# SparkFun_Buck-Boost.net
KiCad netlist of a schematic drawn in EAGLE
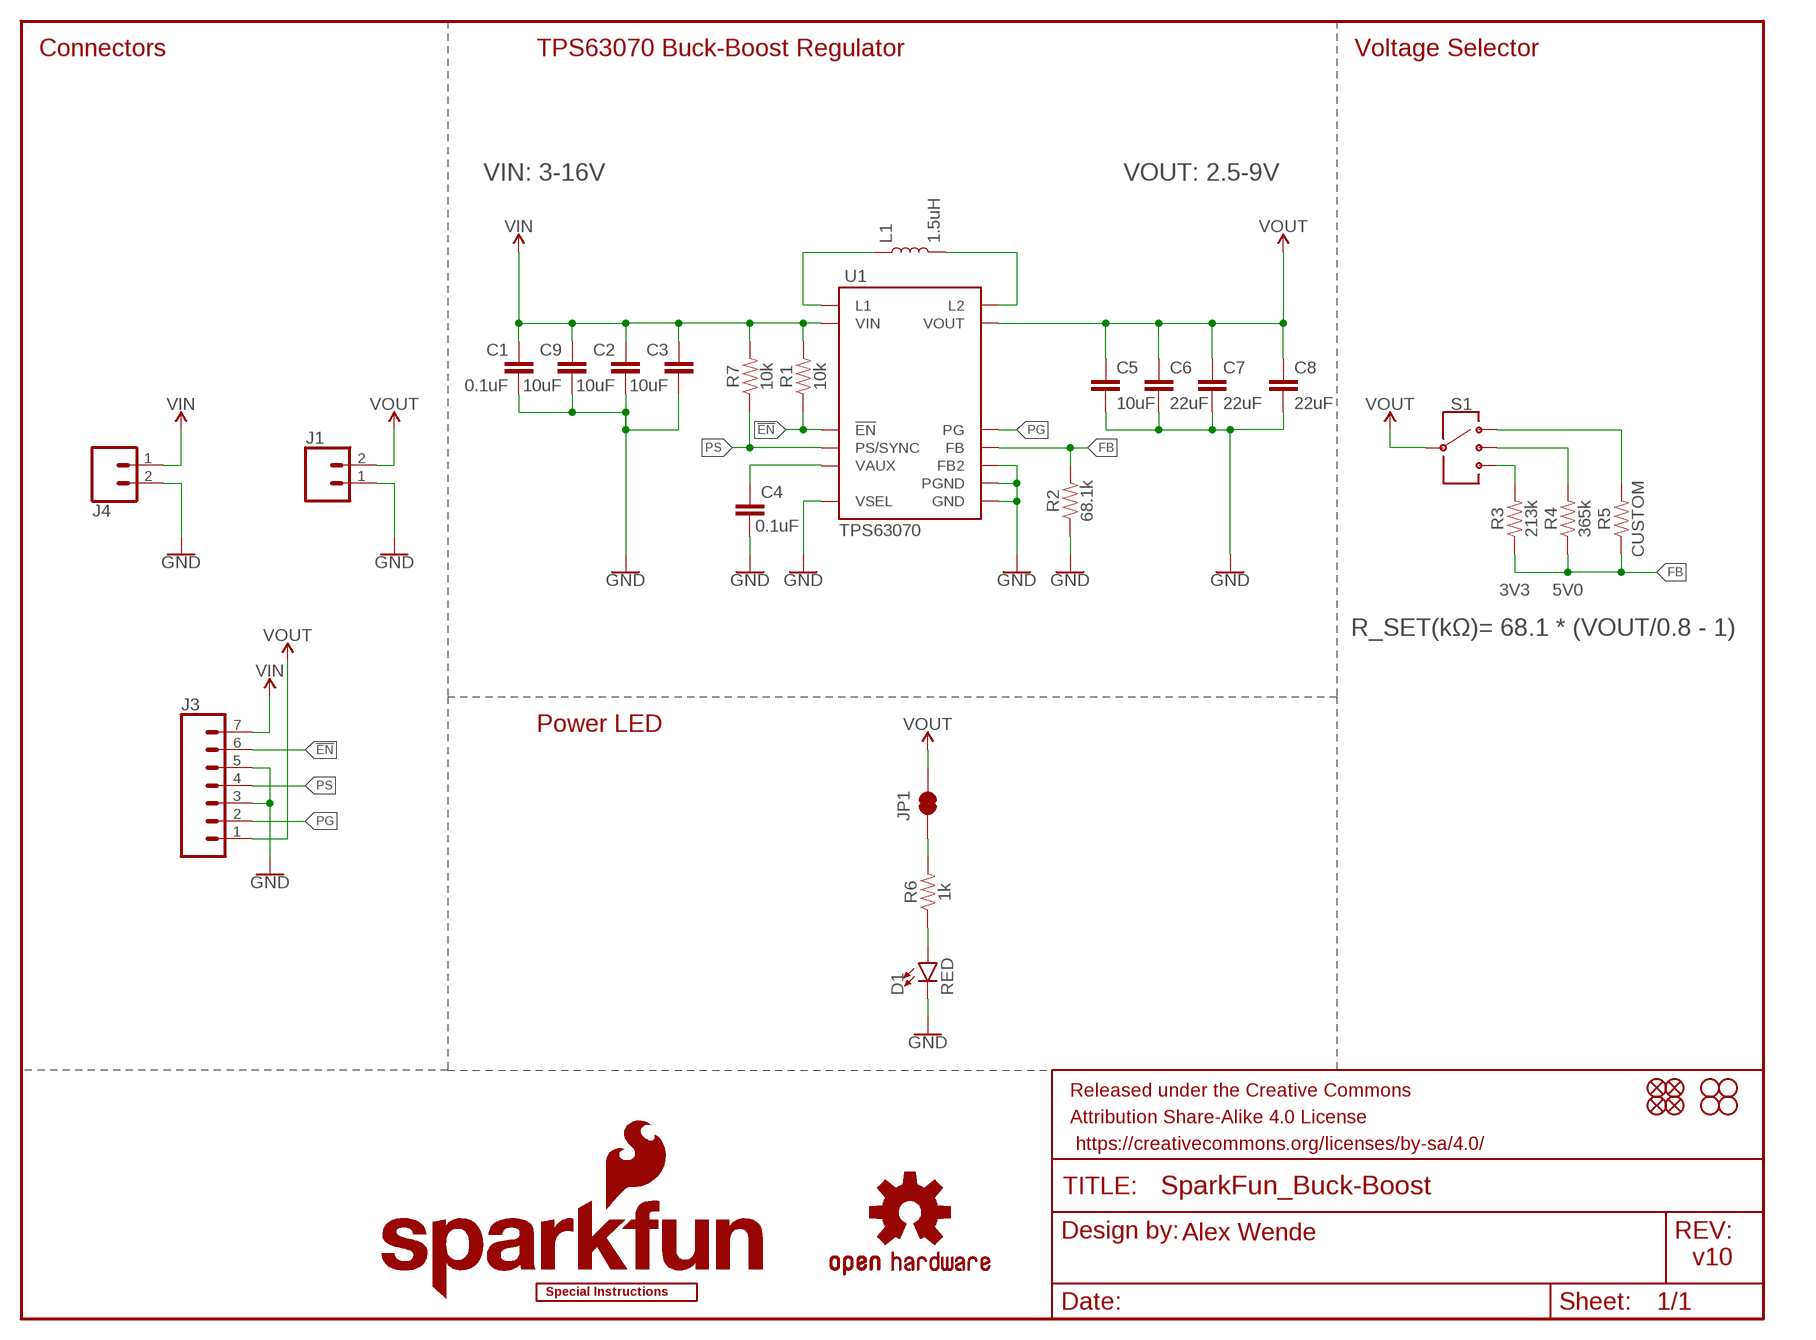
[diagram p0: schematic, sheet 1]

(export (version "E")
  (design (tool "Eeschema 10.0.6"))
  (components
    (comp (ref "C1")
      (value "0.1uF")
      (footprint "eagle-import:0603")
      (libsource (lib "eagle-import") (part "0.1UF-0603-25V-(+80/-20%)"))
    )
    (comp (ref "C2")
      (value "10uF")
      (footprint "eagle-import:0805")
      (libsource (lib "eagle-import") (part "10UF-0805-25V-10%"))
    )
    (comp (ref "C3")
      (value "10uF")
      (footprint "eagle-import:0805")
      (libsource (lib "eagle-import") (part "10UF-0805-25V-10%"))
    )
    (comp (ref "C4")
      (value "0.1uF")
      (footprint "eagle-import:0603")
      (libsource (lib "eagle-import") (part "0.1UF-0603-25V-(+80/-20%)"))
    )
    (comp (ref "C5")
      (value "10uF")
      (footprint "eagle-import:0805")
      (libsource (lib "eagle-import") (part "10UF-0805-25V-10%"))
    )
    (comp (ref "C6")
      (value "22uF")
      (footprint "eagle-import:0805")
      (libsource (lib "eagle-import") (part "22UF-0805-16V-20%"))
    )
    (comp (ref "C7")
      (value "22uF")
      (footprint "eagle-import:0805")
      (libsource (lib "eagle-import") (part "22UF-0805-16V-20%"))
    )
    (comp (ref "C8")
      (value "22uF")
      (footprint "eagle-import:0805")
      (libsource (lib "eagle-import") (part "22UF-0805-16V-20%"))
    )
    (comp (ref "C9")
      (value "10uF")
      (footprint "eagle-import:0805")
      (libsource (lib "eagle-import") (part "10UF-0805-25V-10%"))
    )
    (comp (ref "D1")
      (value "RED")
      (footprint "eagle-import:LED-0603")
      (libsource (lib "eagle-import") (part "LED-RED0603"))
    )
    (comp (ref "FD1")
      (value "FIDUCIALUFIDUCIAL")
      (footprint "eagle-import:FIDUCIAL-MICRO")
      (libsource (lib "eagle-import") (part "FIDUCIALUFIDUCIAL"))
    )
    (comp (ref "FD2")
      (value "FIDUCIALUFIDUCIAL")
      (footprint "eagle-import:FIDUCIAL-MICRO")
      (libsource (lib "eagle-import") (part "FIDUCIALUFIDUCIAL"))
    )
    (comp (ref "FD3")
      (value "FIDUCIALUFIDUCIAL")
      (footprint "eagle-import:FIDUCIAL-MICRO")
      (libsource (lib "eagle-import") (part "FIDUCIALUFIDUCIAL"))
    )
    (comp (ref "FD4")
      (value "FIDUCIALUFIDUCIAL")
      (footprint "eagle-import:FIDUCIAL-MICRO")
      (libsource (lib "eagle-import") (part "FIDUCIALUFIDUCIAL"))
    )
    (comp (ref "FRAME1")
      (value "FRAME-LETTER")
      (footprint "eagle-import:CREATIVE_COMMONS")
      (libsource (lib "eagle-import") (part "FRAME-LETTER"))
    )
    (comp (ref "H1")
      (value "STAND-OFF")
      (footprint "eagle-import:STAND-OFF")
      (libsource (lib "eagle-import") (part "STAND-OFF"))
    )
    (comp (ref "H2")
      (value "STAND-OFF")
      (footprint "eagle-import:STAND-OFF")
      (libsource (lib "eagle-import") (part "STAND-OFF"))
    )
    (comp (ref "H3")
      (value "STAND-OFF")
      (footprint "eagle-import:STAND-OFF")
      (libsource (lib "eagle-import") (part "STAND-OFF"))
    )
    (comp (ref "H4")
      (value "STAND-OFF")
      (footprint "eagle-import:STAND-OFF")
      (libsource (lib "eagle-import") (part "STAND-OFF"))
    )
    (comp (ref "J1")
      (value "CONN_023.5MM-NO_SILK")
      (footprint "eagle-import:SCREWTERMINAL-3.5MM-2-NS")
      (libsource (lib "eagle-import") (part "CONN_023.5MM-NO_SILK"))
    )
    (comp (ref "J3")
      (value "CONN_07NO_SILK")
      (footprint "eagle-import:1X07_NO_SILK")
      (libsource (lib "eagle-import") (part "CONN_07NO_SILK"))
    )
    (comp (ref "J4")
      (value "CONN_023.5MM-NO_SILK")
      (footprint "eagle-import:SCREWTERMINAL-3.5MM-2-NS")
      (libsource (lib "eagle-import") (part "CONN_023.5MM-NO_SILK"))
    )
    (comp (ref "JP1")
      (value "JUMPER-SMT_2_NC_TRACE_NO-SILK")
      (footprint "eagle-import:SMT-JUMPER_2_NC_TRACE_NO-SILK")
      (libsource (lib "eagle-import") (part "JUMPER-SMT_2_NC_TRACE_NO-SILK"))
    )
    (comp (ref "L1")
      (value "1.5uH")
      (footprint "eagle-import:XFL4020")
      (libsource (lib "eagle-import") (part "INDUCTOR-XFL40201.5UH"))
    )
    (comp (ref "LOGO1")
      (value "SFE_LOGO_NAME_FLAME.1_INCH")
      (footprint "eagle-import:SFE_LOGO_NAME_FLAME_.1")
      (libsource (lib "eagle-import") (part "SFE_LOGO_NAME_FLAME.1_INCH"))
    )
    (comp (ref "LOGO2")
      (value "OSHW-LOGOS")
      (footprint "eagle-import:OSHW-LOGO-S")
      (libsource (lib "eagle-import") (part "OSHW-LOGOS"))
    )
    (comp (ref "LOGO3")
      (value "SPECIAL_INSTRUCTIONS-ORDERING")
      (footprint "eagle-import:ORDERING_INSTRUCTIONS")
      (libsource (lib "eagle-import") (part "SPECIAL_INSTRUCTIONS-ORDERING"))
    )
    (comp (ref "R1")
      (value "10k")
      (footprint "eagle-import:0603")
      (libsource (lib "eagle-import") (part "10KOHM-0603-1/10W-1%"))
    )
    (comp (ref "R2")
      (value "68.1k")
      (footprint "eagle-import:0603")
      (libsource (lib "eagle-import") (part "68.1KOHM-0603-1/10W-1%"))
    )
    (comp (ref "R3")
      (value "213k")
      (footprint "eagle-import:0603")
      (libsource (lib "eagle-import") (part "213KOHM-0603-1/10W-0.1%"))
    )
    (comp (ref "R4")
      (value "365k")
      (footprint "eagle-import:0603")
      (libsource (lib "eagle-import") (part "365KOHM-0603-1/10W-1%"))
    )
    (comp (ref "R5")
      (value "CUSTOM")
      (footprint "eagle-import:AXIAL-0.3")
      (libsource (lib "eagle-import") (part "RESISTORAXIAL-0.3"))
    )
    (comp (ref "R6")
      (value "1k")
      (footprint "eagle-import:0603")
      (libsource (lib "eagle-import") (part "1KOHM-0603-1/10W-1%"))
    )
    (comp (ref "R7")
      (value "10k")
      (footprint "eagle-import:0603")
      (libsource (lib "eagle-import") (part "10KOHM-0603-1/10W-1%"))
    )
    (comp (ref "S1")
      (value "SWITCH-SP3T-SMD")
      (footprint "eagle-import:SWITCH_SP3T_SMD")
      (libsource (lib "eagle-import") (part "SWITCH-SP3T-SMD"))
    )
    (comp (ref "U1")
      (value "TPS63070")
      (footprint "eagle-import:VQFN-15-HR(3X2.5)")
      (libsource (lib "eagle-import") (part "TPS63070"))
    )
  )
  (nets
    (net (code "1") (name "/~{EN}") (class "Default")
      (node (ref "J3") (pin "6") (pinfunction "6_6") (pintype "passive"))
      (node (ref "R1") (pin "1") (pinfunction "1_1") (pintype "passive"))
      (node (ref "U1") (pin "P$14") (pinfunction "~{EN}_P$14") (pintype "bidirectional"))
    )
    (net (code "2") (name "FB") (class "Default")
      (node (ref "R2") (pin "2") (pinfunction "2_2") (pintype "passive"))
      (node (ref "R3") (pin "1") (pinfunction "1_1") (pintype "passive"))
      (node (ref "R4") (pin "1") (pinfunction "1_1") (pintype "passive"))
      (node (ref "R5") (pin "P$1") (pinfunction "1_P$1") (pintype "passive"))
      (node (ref "U1") (pin "P$5") (pinfunction "FB_P$5") (pintype "bidirectional"))
    )
    (net (code "3") (name "GND") (class "Default")
      (node (ref "C1") (pin "2") (pinfunction "2_2") (pintype "passive"))
      (node (ref "C2") (pin "2") (pinfunction "2_2") (pintype "passive"))
      (node (ref "C3") (pin "2") (pinfunction "2_2") (pintype "passive"))
      (node (ref "C4") (pin "2") (pinfunction "2_2") (pintype "passive"))
      (node (ref "C5") (pin "2") (pinfunction "2_2") (pintype "passive"))
      (node (ref "C6") (pin "2") (pinfunction "2_2") (pintype "passive"))
      (node (ref "C7") (pin "2") (pinfunction "2_2") (pintype "passive"))
      (node (ref "C8") (pin "2") (pinfunction "2_2") (pintype "passive"))
      (node (ref "C9") (pin "2") (pinfunction "2_2") (pintype "passive"))
      (node (ref "D1") (pin "C") (pinfunction "C_C") (pintype "passive"))
      (node (ref "J1") (pin "1") (pinfunction "1_1") (pintype "passive"))
      (node (ref "J3") (pin "3") (pinfunction "3_3") (pintype "passive"))
      (node (ref "J3") (pin "5") (pinfunction "5_5") (pintype "passive"))
      (node (ref "J4") (pin "2") (pinfunction "2_2") (pintype "passive"))
      (node (ref "R2") (pin "1") (pinfunction "1_1") (pintype "passive"))
      (node (ref "U1") (pin "P$10") (pinfunction "PGND_P$10") (pintype "bidirectional"))
      (node (ref "U1") (pin "P$15") (pinfunction "VSEL_P$15") (pintype "bidirectional"))
      (node (ref "U1") (pin "P$4") (pinfunction "GND_P$4") (pintype "bidirectional"))
      (node (ref "U1") (pin "P$6") (pinfunction "FB2_P$6") (pintype "bidirectional"))
    )
    (net (code "4") (name "Net-(D1-PadA)") (class "Default")
      (node (ref "D1") (pin "A") (pinfunction "A_A") (pintype "passive"))
      (node (ref "R6") (pin "1") (pinfunction "1_1") (pintype "passive"))
    )
    (net (code "5") (name "Net-(JP1-Pad1)") (class "Default")
      (node (ref "JP1") (pin "1") (pinfunction "1_1") (pintype "passive"))
      (node (ref "R6") (pin "2") (pinfunction "2_2") (pintype "passive"))
    )
    (net (code "6") (name "Net-(L1-1)") (class "Default")
      (node (ref "L1") (pin "P$1") (pinfunction "1_P$1") (pintype "passive"))
      (node (ref "U1") (pin "P$11") (pinfunction "L1_P$11") (pintype "bidirectional"))
    )
    (net (code "7") (name "Net-(L1-2)") (class "Default")
      (node (ref "L1") (pin "P$2") (pinfunction "2_P$2") (pintype "passive"))
      (node (ref "U1") (pin "P$9") (pinfunction "L2_P$9") (pintype "bidirectional"))
    )
    (net (code "8") (name "Net-(R3-Pad2)") (class "Default")
      (node (ref "R3") (pin "2") (pinfunction "2_2") (pintype "passive"))
      (node (ref "S1") (pin "4") (pinfunction "4_4") (pintype "bidirectional"))
    )
    (net (code "9") (name "Net-(R4-Pad2)") (class "Default")
      (node (ref "R4") (pin "2") (pinfunction "2_2") (pintype "passive"))
      (node (ref "S1") (pin "2") (pinfunction "2_2") (pintype "bidirectional"))
    )
    (net (code "10") (name "Net-(R5-2)") (class "Default")
      (node (ref "R5") (pin "P$2") (pinfunction "2_P$2") (pintype "passive"))
      (node (ref "S1") (pin "1") (pinfunction "1_1") (pintype "bidirectional"))
    )
    (net (code "11") (name "Net-(U1-VAUX)") (class "Default")
      (node (ref "C4") (pin "1") (pinfunction "1_1") (pintype "passive"))
      (node (ref "U1") (pin "P$3") (pinfunction "VAUX_P$3") (pintype "bidirectional"))
    )
    (net (code "12") (name "PG") (class "Default")
      (node (ref "J3") (pin "2") (pinfunction "2_2") (pintype "passive"))
      (node (ref "U1") (pin "P$2") (pinfunction "PG_P$2") (pintype "bidirectional"))
    )
    (net (code "13") (name "PS") (class "Default")
      (node (ref "J3") (pin "4") (pinfunction "4_4") (pintype "passive"))
      (node (ref "R7") (pin "1") (pinfunction "1_1") (pintype "passive"))
      (node (ref "U1") (pin "P$1") (pinfunction "PS/SYNC_P$1") (pintype "bidirectional"))
    )
    (net (code "14") (name "VIN") (class "Default")
      (node (ref "C1") (pin "1") (pinfunction "1_1") (pintype "passive"))
      (node (ref "C2") (pin "1") (pinfunction "1_1") (pintype "passive"))
      (node (ref "C3") (pin "1") (pinfunction "1_1") (pintype "passive"))
      (node (ref "C9") (pin "1") (pinfunction "1_1") (pintype "passive"))
      (node (ref "J3") (pin "7") (pinfunction "7_7") (pintype "passive"))
      (node (ref "J4") (pin "1") (pinfunction "1_1") (pintype "passive"))
      (node (ref "R1") (pin "2") (pinfunction "2_2") (pintype "passive"))
      (node (ref "R7") (pin "2") (pinfunction "2_2") (pintype "passive"))
      (node (ref "U1") (pin "P$12/13") (pinfunction "VIN_P$12/13") (pintype "bidirectional"))
    )
    (net (code "15") (name "VOUT") (class "Default")
      (node (ref "C5") (pin "1") (pinfunction "1_1") (pintype "passive"))
      (node (ref "C6") (pin "1") (pinfunction "1_1") (pintype "passive"))
      (node (ref "C7") (pin "1") (pinfunction "1_1") (pintype "passive"))
      (node (ref "C8") (pin "1") (pinfunction "1_1") (pintype "passive"))
      (node (ref "J1") (pin "2") (pinfunction "2_2") (pintype "passive"))
      (node (ref "J3") (pin "1") (pinfunction "1_1") (pintype "passive"))
      (node (ref "JP1") (pin "2") (pinfunction "2_2") (pintype "passive"))
      (node (ref "S1") (pin "3") (pinfunction "3_3") (pintype "bidirectional"))
      (node (ref "U1") (pin "P$7/8") (pinfunction "VOUT_P$7/8") (pintype "bidirectional"))
    )
  )
)
